# Encoder.net
KiCad netlist of a schematic drawn in Altium Designer
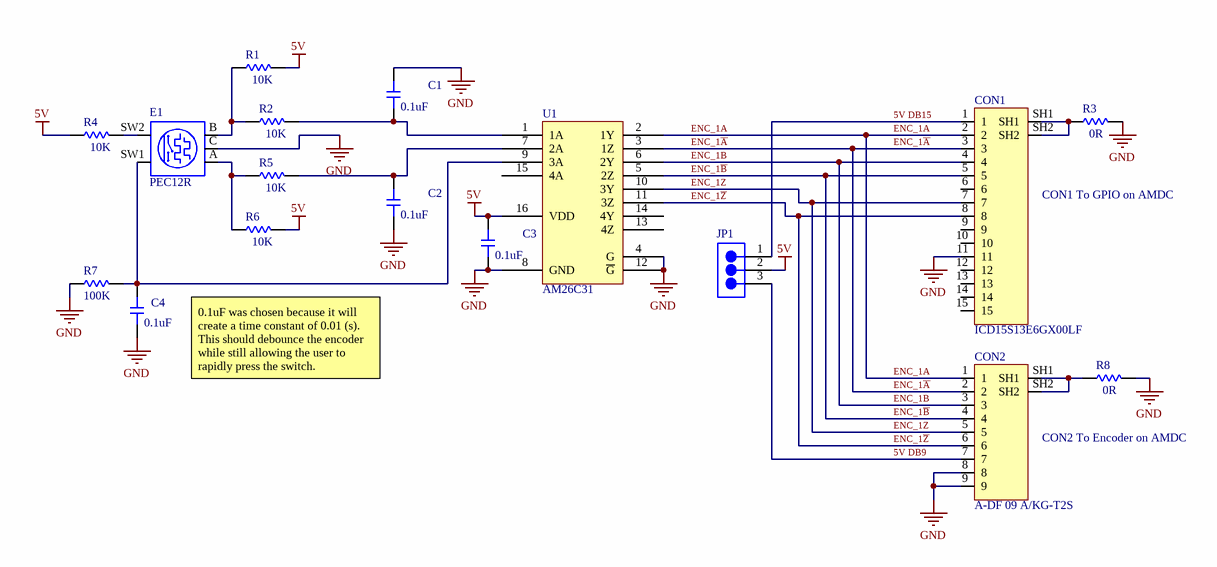
[diagram p0: Encoder.SchDoc]

(export (version "E")
  (design (tool "Eeschema 10.0.6"))
  (components
    (comp (ref "C1")
      (value "Capacitor 0.1uF")
      (footprint ".1uF Capacitor (0603-CAP)")
      (description "Capacitor")
      (libsource (lib "Encoder") (part "Capacitor 0.1uF"))
    )
    (comp (ref "C2")
      (value "Capacitor 0.1uF")
      (footprint ".1uF Capacitor (0603-CAP)")
      (description "Capacitor")
      (libsource (lib "Encoder") (part "Capacitor 0.1uF"))
    )
    (comp (ref "C3")
      (value "Capacitor 0.1uF")
      (footprint ".1uF Capacitor (0603-CAP)")
      (description "Capacitor")
      (libsource (lib "Encoder") (part "Capacitor 0.1uF"))
    )
    (comp (ref "C4")
      (value "Capacitor 0.1uF")
      (footprint ".1uF Capacitor (0603-CAP)")
      (description "Capacitor")
      (libsource (lib "Encoder") (part "Capacitor 0.1uF"))
    )
    (comp (ref "CON1")
      (value "ICD15S13E6GX00LF")
      (footprint "ICD15S")
      (description "CONN D-SUB PLUG 15POS R/A SLDR")
      (libsource (lib "Encoder") (part "ICD15S13E6GX00LF"))
    )
    (comp (ref "CON2")
      (value "A-DF 09 A/KG-T2S")
      (footprint "DB9 Connector")
      (description "9 Position D-Sub Receptacle, Female Sockets Connector")
      (fields (field (name "MF") "Assmann WSW"))
      (libsource (lib "Encoder") (part "DB9 Connector A-DF_09_A/KG-T2S"))
    )
    (comp (ref "E1")
      (value "PEC12R")
      (footprint "Encoder")
      (libsource (lib "Encoder") (part "PEC12R-4220F-S0024"))
    )
    (comp (ref "JP1")
      (value "Jumper3")
      (footprint "PIN_HEADER_1X3")
      (libsource (lib "Encoder") (part "Jumper3"))
    )
    (comp (ref "R1")
      (value "Resistor")
      (footprint "10K Resistor (0603-RES)")
      (libsource (lib "Encoder") (part "Resistor 10K"))
    )
    (comp (ref "R2")
      (value "Resistor")
      (footprint "10K Resistor (0603-RES)")
      (libsource (lib "Encoder") (part "Resistor 10K"))
    )
    (comp (ref "R3")
      (value "Resistor")
      (footprint "0 Resistor (1206-RES)")
      (libsource (lib "Encoder") (part "Resistor 0R"))
    )
    (comp (ref "R4")
      (value "Resistor")
      (footprint "10K Resistor (0603-RES)")
      (libsource (lib "Encoder") (part "Resistor 10K"))
    )
    (comp (ref "R5")
      (value "Resistor")
      (footprint "10K Resistor (0603-RES)")
      (libsource (lib "Encoder") (part "Resistor 10K"))
    )
    (comp (ref "R6")
      (value "Resistor")
      (footprint "10K Resistor (0603-RES)")
      (libsource (lib "Encoder") (part "Resistor 10K"))
    )
    (comp (ref "R7")
      (value "Resistor")
      (footprint "100K Resistor (0603-RES)")
      (libsource (lib "Encoder") (part "Resistor 100K"))
    )
    (comp (ref "R8")
      (value "Resistor")
      (footprint "0 Resistor (1206-RES)")
      (libsource (lib "Encoder") (part "Resistor 0R"))
    )
    (comp (ref "U1")
      (value "AM26C31")
      (footprint "AM26C31")
      (description "IC DRIVER 4/0 16TSSOP")
      (libsource (lib "Encoder") (part "AM26C31"))
    )
  )
  (nets
    (net (code "1") (name "/5V DB9") (class "Default")
      (node (ref "CON2") (pin "7") (pinfunction "7_7") (pintype "passive"))
      (node (ref "JP1") (pin "3") (pinfunction "75_3") (pintype "passive"))
    )
    (net (code "2") (name "/5V DB15") (class "Default")
      (node (ref "CON1") (pin "1") (pinfunction "1_1") (pintype "passive"))
      (node (ref "JP1") (pin "1") (pinfunction "76_1") (pintype "passive"))
    )
    (net (code "3") (name "/ENC_1A") (class "Default")
      (node (ref "CON1") (pin "2") (pinfunction "2_2") (pintype "passive"))
      (node (ref "CON2") (pin "1") (pinfunction "1_1") (pintype "passive"))
      (node (ref "U1") (pin "2") (pinfunction "1Y_2") (pintype "passive"))
    )
    (net (code "4") (name "/ENC_1B") (class "Default")
      (node (ref "CON1") (pin "4") (pinfunction "4_4") (pintype "passive"))
      (node (ref "CON2") (pin "3") (pinfunction "3_3") (pintype "passive"))
      (node (ref "U1") (pin "6") (pinfunction "2Y_6") (pintype "passive"))
    )
    (net (code "5") (name "/ENC_1Z") (class "Default")
      (node (ref "CON1") (pin "7") (pinfunction "7_7") (pintype "passive"))
      (node (ref "CON2") (pin "5") (pinfunction "5_5") (pintype "passive"))
      (node (ref "U1") (pin "10") (pinfunction "3Y_10") (pintype "passive"))
    )
    (net (code "6") (name "/ENC_1~{A}") (class "Default")
      (node (ref "CON1") (pin "3") (pinfunction "3_3") (pintype "passive"))
      (node (ref "CON2") (pin "2") (pinfunction "2_2") (pintype "passive"))
      (node (ref "U1") (pin "3") (pinfunction "1Z_3") (pintype "passive"))
    )
    (net (code "7") (name "/ENC_1~{B}") (class "Default")
      (node (ref "CON1") (pin "5") (pinfunction "5_5") (pintype "passive"))
      (node (ref "CON2") (pin "4") (pinfunction "4_4") (pintype "passive"))
      (node (ref "U1") (pin "5") (pinfunction "2Z_5") (pintype "passive"))
    )
    (net (code "8") (name "/ENC_1~{Z}") (class "Default")
      (node (ref "CON1") (pin "8") (pinfunction "8_8") (pintype "passive"))
      (node (ref "CON2") (pin "6") (pinfunction "6_6") (pintype "passive"))
      (node (ref "U1") (pin "11") (pinfunction "3Z_11") (pintype "passive"))
    )
    (net (code "9") (name "5V") (class "Default")
      (node (ref "C3") (pin "1") (pinfunction "1_1") (pintype "passive"))
      (node (ref "JP1") (pin "2") (pinfunction "75_2") (pintype "passive"))
      (node (ref "R1") (pin "2") (pinfunction "2_2") (pintype "passive"))
      (node (ref "R4") (pin "1") (pinfunction "1_1") (pintype "passive"))
      (node (ref "R6") (pin "2") (pinfunction "2_2") (pintype "passive"))
      (node (ref "U1") (pin "16") (pinfunction "VDD_16") (pintype "passive"))
    )
    (net (code "10") (name "GND") (class "Default")
      (node (ref "C1") (pin "1") (pinfunction "1_1") (pintype "passive"))
      (node (ref "C2") (pin "2") (pinfunction "2_2") (pintype "passive"))
      (node (ref "C3") (pin "2") (pinfunction "2_2") (pintype "passive"))
      (node (ref "C4") (pin "2") (pinfunction "2_2") (pintype "passive"))
      (node (ref "CON1") (pin "11") (pinfunction "11_11") (pintype "passive"))
      (node (ref "CON2") (pin "8") (pinfunction "8_8") (pintype "passive"))
      (node (ref "CON2") (pin "9") (pinfunction "9_9") (pintype "passive"))
      (node (ref "E1") (pin "C") (pinfunction "C_C") (pintype "passive"))
      (node (ref "R3") (pin "2") (pinfunction "2_2") (pintype "passive"))
      (node (ref "R7") (pin "1") (pinfunction "1_1") (pintype "passive"))
      (node (ref "R8") (pin "2") (pinfunction "2_2") (pintype "passive"))
      (node (ref "U1") (pin "12") (pinfunction "~{G}_12") (pintype "passive"))
      (node (ref "U1") (pin "4") (pinfunction "G_4") (pintype "passive"))
      (node (ref "U1") (pin "8") (pinfunction "GND_8") (pintype "passive"))
    )
    (net (code "11") (name "Net-(CON1-PadSH1)") (class "Default")
      (node (ref "CON1") (pin "SH1") (pinfunction "SH1_SH1") (pintype "passive"))
      (node (ref "CON1") (pin "SH2") (pinfunction "SH2_SH2") (pintype "passive"))
      (node (ref "R3") (pin "1") (pinfunction "1_1") (pintype "passive"))
    )
    (net (code "12") (name "Net-(CON2-PadSH1)") (class "Default")
      (node (ref "CON2") (pin "SH1") (pinfunction "SH1_SH1") (pintype "passive"))
      (node (ref "CON2") (pin "SH2") (pinfunction "SH2_SH2") (pintype "passive"))
      (node (ref "R8") (pin "1") (pinfunction "1_1") (pintype "passive"))
    )
    (net (code "13") (name "Net-(E1-PadA)") (class "Default")
      (node (ref "E1") (pin "A") (pinfunction "A_A") (pintype "passive"))
      (node (ref "R5") (pin "1") (pinfunction "1_1") (pintype "passive"))
      (node (ref "R6") (pin "1") (pinfunction "1_1") (pintype "passive"))
    )
    (net (code "14") (name "Net-(E1-PadB)") (class "Default")
      (node (ref "E1") (pin "B") (pinfunction "B_B") (pintype "passive"))
      (node (ref "R1") (pin "1") (pinfunction "1_1") (pintype "passive"))
      (node (ref "R2") (pin "1") (pinfunction "1_1") (pintype "passive"))
    )
    (net (code "15") (name "Net-(E1-PadSW2)") (class "Default")
      (node (ref "E1") (pin "SW2") (pinfunction "SW2_SW2") (pintype "passive"))
      (node (ref "R4") (pin "2") (pinfunction "2_2") (pintype "passive"))
    )
    (net (code "16") (name "Net-(U1-1A)") (class "Default")
      (node (ref "C1") (pin "2") (pinfunction "2_2") (pintype "passive"))
      (node (ref "R2") (pin "2") (pinfunction "2_2") (pintype "passive"))
      (node (ref "U1") (pin "1") (pinfunction "1A_1") (pintype "passive"))
    )
    (net (code "17") (name "Net-(U1-2A)") (class "Default")
      (node (ref "C2") (pin "1") (pinfunction "1_1") (pintype "passive"))
      (node (ref "R5") (pin "2") (pinfunction "2_2") (pintype "passive"))
      (node (ref "U1") (pin "7") (pinfunction "2A_7") (pintype "passive"))
    )
    (net (code "18") (name "Net-(U1-3A)") (class "Default")
      (node (ref "C4") (pin "1") (pinfunction "1_1") (pintype "passive"))
      (node (ref "E1") (pin "SW1") (pinfunction "SW1_SW1") (pintype "passive"))
      (node (ref "R7") (pin "2") (pinfunction "2_2") (pintype "passive"))
      (node (ref "U1") (pin "9") (pinfunction "3A_9") (pintype "passive"))
    )
    (net (code "19") (name "unconnected-(CON1-Pad6)") (class "Default")
      (node (ref "CON1") (pin "6") (pinfunction "6_6") (pintype "passive"))
    )
    (net (code "20") (name "unconnected-(CON1-Pad9)") (class "Default")
      (node (ref "CON1") (pin "9") (pinfunction "9_9") (pintype "passive"))
    )
    (net (code "21") (name "unconnected-(CON1-Pad10)") (class "Default")
      (node (ref "CON1") (pin "10") (pinfunction "10_10") (pintype "passive"))
    )
    (net (code "22") (name "unconnected-(CON1-Pad12)") (class "Default")
      (node (ref "CON1") (pin "12") (pinfunction "12_12") (pintype "passive"))
    )
    (net (code "23") (name "unconnected-(CON1-Pad13)") (class "Default")
      (node (ref "CON1") (pin "13") (pinfunction "13_13") (pintype "passive"))
    )
    (net (code "24") (name "unconnected-(CON1-Pad14)") (class "Default")
      (node (ref "CON1") (pin "14") (pinfunction "14_14") (pintype "passive"))
    )
    (net (code "25") (name "unconnected-(CON1-Pad15)") (class "Default")
      (node (ref "CON1") (pin "15") (pinfunction "15_15") (pintype "passive"))
    )
    (net (code "26") (name "unconnected-(U1-4A-Pad15)") (class "Default")
      (node (ref "U1") (pin "15") (pinfunction "4A_15") (pintype "passive"))
    )
    (net (code "27") (name "unconnected-(U1-4Y-Pad14)") (class "Default")
      (node (ref "U1") (pin "14") (pinfunction "4Y_14") (pintype "passive"))
    )
    (net (code "28") (name "unconnected-(U1-4Z-Pad13)") (class "Default")
      (node (ref "U1") (pin "13") (pinfunction "4Z_13") (pintype "passive"))
    )
  )
)
